# SharkPup-System.net
KiCad netlist of a schematic drawn in Altium Designer
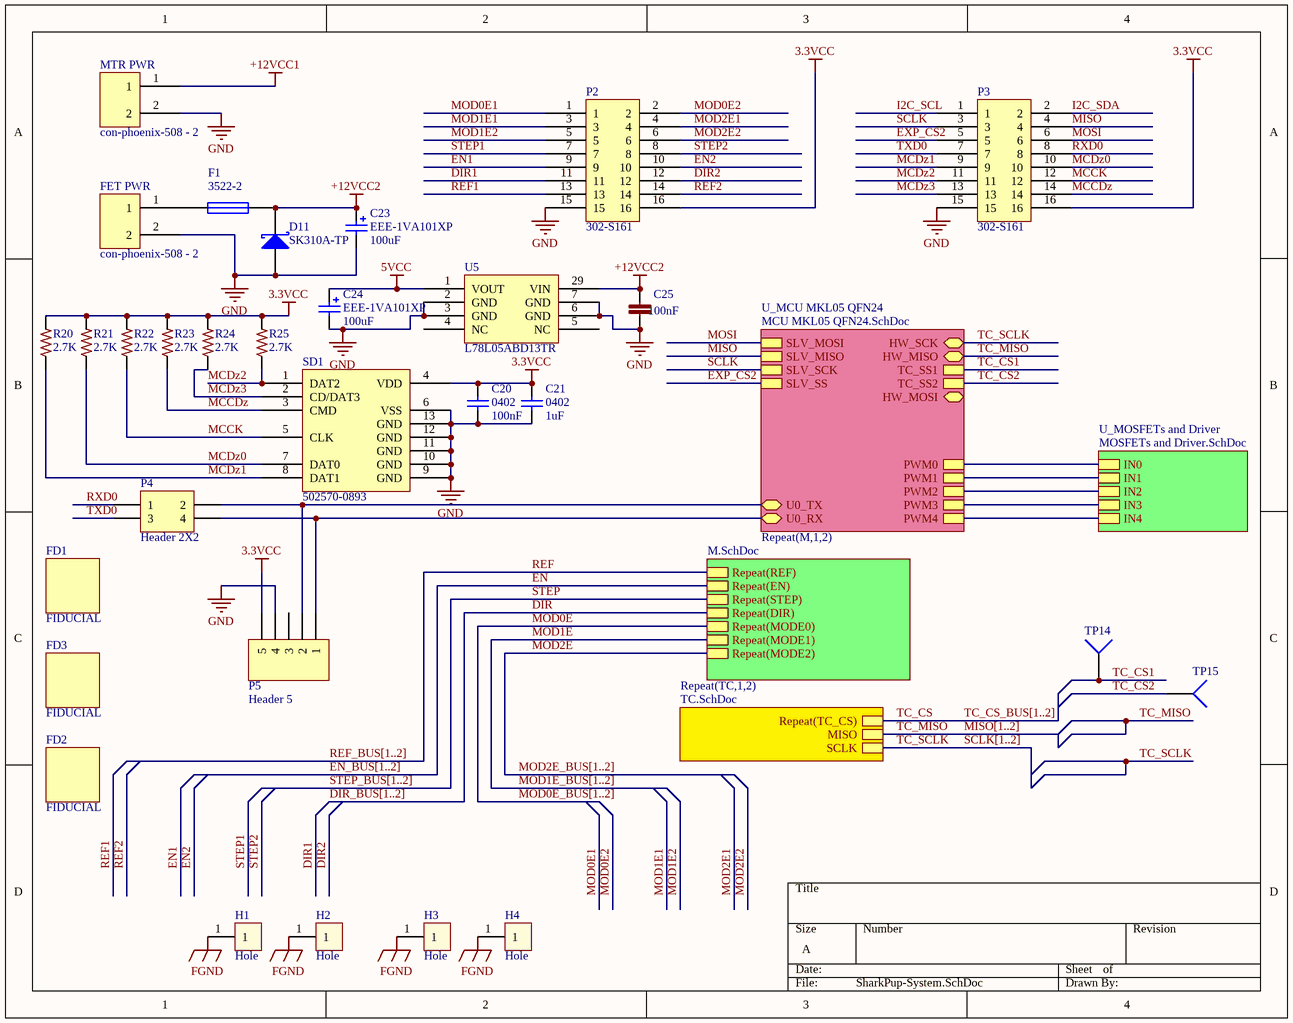
[diagram p0: SharkPup-System.SchDoc]

(export (version "E")
  (design (tool "Eeschema 10.0.6"))
  (components
    (comp (ref "C20")
      (value "100nF")
      (footprint "C0402")
      (description "CAP CER 0.1UF (100nF) 16V 10% X7R 0402")
      (fields
        (field (name "MFR PART #") "GRM155R71C104KA88D")
        (field (name "MFR") "Murata")
        (field (name "PACKAGEREFERENCE") "0402")
        (field (name "PUBLISHER") "Ultimachine")
      )
      (libsource (lib "Tigershark3D") (part "GRM155R71C104KA88D"))
    )
    (comp (ref "C21")
      (value "1uF")
      (footprint "C0402")
      (description "CAP CER 1UF 6.3V 10% X5R 0402")
      (fields
        (field (name "MFR PART #") "GRM155R60J105KE19D")
        (field (name "MFR") "Murata")
        (field (name "PACKAGEREFERENCE") "0402")
        (field (name "PUBLISHER") "Ultimachine")
      )
      (libsource (lib "Tigershark3D") (part "GRM155R60J105KE19D"))
    )
    (comp (ref "C23")
      (value "EEE-1VA101XP")
      (footprint "EEE-1VA101XP")
      (description "CAP ALUM 100UF 35V 20% SMD")
      (fields (field (name "DIGIKEY PART #") "PCE3951CT-ND") (field (name "ALTIUM_VALUE") "100uF"))
      (libsource (lib "Tigershark3D") (part "EEE-1VA101XP"))
    )
    (comp (ref "C24")
      (value "EEE-1VA101XP")
      (footprint "EEE-1VA101XP")
      (description "CAP ALUM 100UF 35V 20% SMD")
      (fields (field (name "DIGIKEY PART #") "PCE3951CT-ND") (field (name "ALTIUM_VALUE") "100uF"))
      (libsource (lib "Tigershark3D") (part "EEE-1VA101XP"))
    )
    (comp (ref "C25")
      (value "100nF")
      (footprint "C0603")
      (description "CAP CER 0603 100nF 50V 10% X7R")
      (fields
        (field (name "MANUFACTURERPARTNUMBER") "C0603C104K5RACTU")
        (field (name "PUBLISHER") "UltiMachine")
      )
      (libsource (lib "Tigershark3D") (part "C0603C104K5RACTU"))
    )
    (comp (ref "D11")
      (value "SK310A-TP")
      (footprint "SK310A-TP")
      (description "Schottky Diode")
      (fields (field (name "PUBLISHER") "Altium Limited"))
      (libsource (lib "Miscellaneous Devices") (part "D Schottky"))
    )
    (comp (ref "F1")
      (value "3522-2")
      (footprint "3522-2 - WAVE SOLDER")
      (description "Fuse")
      (fields (field (name "PUBLISHER") "Altium Limited"))
      (libsource (lib "Miscellaneous Devices") (part "Fuse 1"))
    )
    (comp (ref "FD1")
      (value "FIDUCIAL")
      (footprint "FIDUCIAL-1X2")
      (libsource (lib "ZMBo Schematic Library") (part "FIDUCIAL"))
    )
    (comp (ref "FD2")
      (value "FIDUCIAL")
      (footprint "FIDUCIAL-1X2")
      (libsource (lib "ZMBo Schematic Library") (part "FIDUCIAL"))
    )
    (comp (ref "FD3")
      (value "FIDUCIAL")
      (footprint "FIDUCIAL-1X2")
      (libsource (lib "ZMBo Schematic Library") (part "FIDUCIAL"))
    )
    (comp (ref "FET PWR")
      (value "con-phoenix-508 - 2")
      (footprint "MSTBV2 - duplicate")
      (libsource (lib "ZMBo Schematic Library") (part "con-phoenix-508_2"))
    )
    (comp (ref "H1")
      (value "Hole")
      (footprint "Wave_hole_3x7-singleSided")
      (libsource (lib "3Delight") (part "Hole"))
    )
    (comp (ref "H2")
      (value "Hole")
      (footprint "Wave_hole_3x7-singleSided")
      (libsource (lib "3Delight") (part "Hole"))
    )
    (comp (ref "H3")
      (value "Hole")
      (footprint "Wave_hole_3x7-singleSided")
      (libsource (lib "3Delight") (part "Hole"))
    )
    (comp (ref "H4")
      (value "Hole")
      (footprint "Wave_hole_3x7-singleSided")
      (libsource (lib "3Delight") (part "Hole"))
    )
    (comp (ref "MTR PWR")
      (value "con-phoenix-508 - 2")
      (footprint "MSTBV2 - duplicate")
      (libsource (lib "ZMBo Schematic Library") (part "con-phoenix-508_2"))
    )
    (comp (ref "P2")
      (value "302-S161")
      (footprint "302-S161")
      (description "16 Pos 2.54mm Pin Connector Shrouded")
      (fields (field (name "DIGIKEY PART #") "ED10522-ND"))
      (libsource (lib "Tigershark3D") (part "302-S161"))
    )
    (comp (ref "P3")
      (value "302-S161")
      (footprint "302-S161")
      (description "16 Pos 2.54mm Pin Connector Shrouded")
      (fields (field (name "DIGIKEY PART #") "ED10522-ND"))
      (libsource (lib "Tigershark3D") (part "302-S161"))
    )
    (comp (ref "P4")
      (value "Header 2X2")
      (footprint "HDR2X2")
      (description "Header, 2-Pin, Dual row")
      (fields (field (name "PUBLISHER") "Altium Limited"))
      (libsource (lib "Miscellaneous Connectors") (part "Header 2X2"))
    )
    (comp (ref "P5")
      (value "Header 5")
      (footprint "HDR1X5")
      (description "Header, 5-Pin")
      (fields (field (name "PUBLISHER") "Altium Limited"))
      (libsource (lib "Miscellaneous Connectors") (part "Header 5"))
    )
    (comp (ref "R20")
      (value "2.7K")
      (footprint "R0402")
      (description "RES SMD 2.7K OHM 1% 1/10W 0402")
      (fields
        (field (name "MANUFACTURER") "Panasonic")
        (field (name "MANUFACTURERPARTNUMBER") "ERJ2GEJ105X")
        (field (name "PUBLISHER") "Adam")
      )
      (libsource (lib "Tigershark3D") (part "ERJ-2RKF2701X"))
    )
    (comp (ref "R21")
      (value "2.7K")
      (footprint "R0402")
      (description "RES SMD 2.7K OHM 1% 1/10W 0402")
      (fields
        (field (name "MANUFACTURER") "Panasonic")
        (field (name "MANUFACTURERPARTNUMBER") "ERJ2GEJ105X")
        (field (name "PUBLISHER") "Adam")
      )
      (libsource (lib "Tigershark3D") (part "ERJ-2RKF2701X"))
    )
    (comp (ref "R22")
      (value "2.7K")
      (footprint "R0402")
      (description "RES SMD 2.7K OHM 1% 1/10W 0402")
      (fields
        (field (name "MANUFACTURER") "Panasonic")
        (field (name "MANUFACTURERPARTNUMBER") "ERJ2GEJ105X")
        (field (name "PUBLISHER") "Adam")
      )
      (libsource (lib "Tigershark3D") (part "ERJ-2RKF2701X"))
    )
    (comp (ref "R23")
      (value "2.7K")
      (footprint "R0402")
      (description "RES SMD 2.7K OHM 1% 1/10W 0402")
      (fields
        (field (name "MANUFACTURER") "Panasonic")
        (field (name "MANUFACTURERPARTNUMBER") "ERJ2GEJ105X")
        (field (name "PUBLISHER") "Adam")
      )
      (libsource (lib "Tigershark3D") (part "ERJ-2RKF2701X"))
    )
    (comp (ref "R24")
      (value "2.7K")
      (footprint "R0402")
      (description "RES SMD 2.7K OHM 1% 1/10W 0402")
      (fields
        (field (name "MANUFACTURER") "Panasonic")
        (field (name "MANUFACTURERPARTNUMBER") "ERJ2GEJ105X")
        (field (name "PUBLISHER") "Adam")
      )
      (libsource (lib "Tigershark3D") (part "ERJ-2RKF2701X"))
    )
    (comp (ref "R25")
      (value "2.7K")
      (footprint "R0402")
      (description "RES SMD 2.7K OHM 1% 1/10W 0402")
      (fields
        (field (name "MANUFACTURER") "Panasonic")
        (field (name "MANUFACTURERPARTNUMBER") "ERJ2GEJ105X")
        (field (name "PUBLISHER") "Adam")
      )
      (libsource (lib "Tigershark3D") (part "ERJ-2RKF2701X"))
    )
    (comp (ref "SD1")
      (value "502570-0893")
      (footprint "502570-0893 - Molex SD")
      (description "microSD 502570-0893 Molex Part")
      (libsource (lib "Tigershark3D") (part "502570-0893"))
    )
    (comp (ref "TP14")
      (value "TP4")
      (footprint "TP-2")
      (description "Socket")
      (fields (field (name "PUBLISHER") "Altium Limited"))
      (libsource (lib "ZMBo Schematic Library") (part "Socket"))
    )
    (comp (ref "TP15")
      (value "TP4")
      (footprint "TP-2")
      (description "Socket")
      (fields (field (name "PUBLISHER") "Altium Limited"))
      (libsource (lib "ZMBo Schematic Library") (part "Socket"))
    )
    (comp (ref "U5")
      (value "L78L05ABD13TR")
      (footprint "L78L05ABD13TR")
      (description "IC REG LDO 5V 0.1A 8SO")
      (fields (field (name "MANUFACTURER") "ST Microelectronics") (field (name "VOLTAGE") "30V"))
      (libsource (lib "SharkPup") (part "L78L05ABD13TR"))
    )
  )
  (nets
    (net (code "21") (name "+12VCC1") (class "Default")
      (node (ref "MTR PWR") (pin "1") (pinfunction "1_1") (pintype "passive"))
    )
    (net (code "22") (name "+12VCC2") (class "Default")
      (node (ref "C23") (pin "1") (pinfunction "1_1") (pintype "passive"))
      (node (ref "C25") (pin "1") (pinfunction "1_1") (pintype "passive"))
      (node (ref "D11") (pin "2") (pinfunction "K_2") (pintype "passive"))
      (node (ref "F1") (pin "2") (pinfunction "2_2") (pintype "passive"))
      (node (ref "U5") (pin "29") (pinfunction "VIN_29") (pintype "passive"))
    )
    (net (code "24") (name "/DIR1") (class "Default")
      (node (ref "P2") (pin "11") (pinfunction "11_11") (pintype "passive"))
    )
    (net (code "25") (name "/DIR2") (class "Default")
      (node (ref "P2") (pin "12") (pinfunction "12_12") (pintype "passive"))
    )
    (net (code "28") (name "/EN1") (class "Default")
      (node (ref "P2") (pin "9") (pinfunction "9_9") (pintype "passive"))
    )
    (net (code "29") (name "/EN2") (class "Default")
      (node (ref "P2") (pin "10") (pinfunction "10_10") (pintype "passive"))
    )
    (net (code "31") (name "/EXP_CS2") (class "Default")
      (node (ref "P3") (pin "5") (pinfunction "5_5") (pintype "passive"))
    )
    (net (code "33") (name "/I2C_SCL") (class "Default")
      (node (ref "P3") (pin "1") (pinfunction "1_1") (pintype "passive"))
    )
    (net (code "34") (name "/I2C_SDA") (class "Default")
      (node (ref "P3") (pin "2") (pinfunction "2_2") (pintype "passive"))
    )
    (net (code "40") (name "/MCCDz") (class "Default")
      (node (ref "P3") (pin "14") (pinfunction "14_14") (pintype "passive"))
      (node (ref "R23") (pin "1") (pinfunction "1_1") (pintype "passive"))
      (node (ref "SD1") (pin "3") (pinfunction "CMD_3") (pintype "passive"))
    )
    (net (code "41") (name "/MCCK") (class "Default")
      (node (ref "P3") (pin "12") (pinfunction "12_12") (pintype "passive"))
      (node (ref "R22") (pin "1") (pinfunction "1_1") (pintype "passive"))
      (node (ref "SD1") (pin "5") (pinfunction "CLK_5") (pintype "passive"))
    )
    (net (code "42") (name "/MCDz0") (class "Default")
      (node (ref "P3") (pin "10") (pinfunction "10_10") (pintype "passive"))
      (node (ref "R21") (pin "1") (pinfunction "1_1") (pintype "passive"))
      (node (ref "SD1") (pin "7") (pinfunction "DAT0_7") (pintype "passive"))
    )
    (net (code "43") (name "/MCDz1") (class "Default")
      (node (ref "P3") (pin "9") (pinfunction "9_9") (pintype "passive"))
      (node (ref "R20") (pin "1") (pinfunction "1_1") (pintype "passive"))
      (node (ref "SD1") (pin "8") (pinfunction "DAT1_8") (pintype "passive"))
    )
    (net (code "44") (name "/MCDz2") (class "Default")
      (node (ref "P3") (pin "11") (pinfunction "11_11") (pintype "passive"))
      (node (ref "R25") (pin "1") (pinfunction "1_1") (pintype "passive"))
      (node (ref "SD1") (pin "1") (pinfunction "DAT2_1") (pintype "passive"))
    )
    (net (code "45") (name "/MCDz3") (class "Default")
      (node (ref "P3") (pin "13") (pinfunction "13_13") (pintype "passive"))
      (node (ref "R24") (pin "1") (pinfunction "1_1") (pintype "passive"))
      (node (ref "SD1") (pin "2") (pinfunction "CD/DAT3_2") (pintype "passive"))
    )
    (net (code "46") (name "/MISO") (class "Default")
      (node (ref "P3") (pin "4") (pinfunction "4_4") (pintype "passive"))
    )
    (net (code "49") (name "/MOD0E1") (class "Default")
      (node (ref "P2") (pin "1") (pinfunction "1_1") (pintype "passive"))
    )
    (net (code "50") (name "/MOD0E2") (class "Default")
      (node (ref "P2") (pin "2") (pinfunction "2_2") (pintype "passive"))
    )
    (net (code "53") (name "/MOD1E1") (class "Default")
      (node (ref "P2") (pin "3") (pinfunction "3_3") (pintype "passive"))
    )
    (net (code "54") (name "/MOD1E2") (class "Default")
      (node (ref "P2") (pin "5") (pinfunction "5_5") (pintype "passive"))
    )
    (net (code "57") (name "/MOD2E1") (class "Default")
      (node (ref "P2") (pin "4") (pinfunction "4_4") (pintype "passive"))
    )
    (net (code "58") (name "/MOD2E2") (class "Default")
      (node (ref "P2") (pin "6") (pinfunction "6_6") (pintype "passive"))
    )
    (net (code "60") (name "/MOSI") (class "Default")
      (node (ref "P3") (pin "6") (pinfunction "6_6") (pintype "passive"))
    )
    (net (code "62") (name "/REF1") (class "Default")
      (node (ref "P2") (pin "13") (pinfunction "13_13") (pintype "passive"))
    )
    (net (code "63") (name "/REF2") (class "Default")
      (node (ref "P2") (pin "14") (pinfunction "14_14") (pintype "passive"))
    )
    (net (code "65") (name "/RXD0") (class "Default")
      (node (ref "P3") (pin "8") (pinfunction "8_8") (pintype "passive"))
      (node (ref "P4") (pin "1") (pinfunction "1_1") (pintype "passive"))
    )
    (net (code "66") (name "/SCLK") (class "Default")
      (node (ref "P3") (pin "3") (pinfunction "3_3") (pintype "passive"))
    )
    (net (code "69") (name "/STEP1") (class "Default")
      (node (ref "P2") (pin "7") (pinfunction "7_7") (pintype "passive"))
    )
    (net (code "70") (name "/STEP2") (class "Default")
      (node (ref "P2") (pin "8") (pinfunction "8_8") (pintype "passive"))
    )
    (net (code "73") (name "/TC_CS1") (class "Default")
      (node (ref "TP14") (pin "1") (pinfunction "1_1") (pintype "passive"))
    )
    (net (code "74") (name "/TC_CS2") (class "Default")
      (node (ref "TP15") (pin "1") (pinfunction "1_1") (pintype "passive"))
    )
    (net (code "78") (name "/TXD0") (class "Default")
      (node (ref "P3") (pin "7") (pinfunction "7_7") (pintype "passive"))
      (node (ref "P4") (pin "3") (pinfunction "3_3") (pintype "passive"))
    )
    (net (code "79") (name "/U0_RX") (class "Default")
      (node (ref "P4") (pin "4") (pinfunction "4_4") (pintype "passive"))
      (node (ref "P5") (pin "1") (pinfunction "1_1") (pintype "passive"))
    )
    (net (code "80") (name "/U0_TX") (class "Default")
      (node (ref "P4") (pin "2") (pinfunction "2_2") (pintype "passive"))
      (node (ref "P5") (pin "2") (pinfunction "2_2") (pintype "passive"))
    )
    (net (code "81") (name "3.3VCC") (class "Default")
      (node (ref "C20") (pin "2") (pinfunction "2_2") (pintype "passive"))
      (node (ref "C21") (pin "2") (pinfunction "2_2") (pintype "passive"))
      (node (ref "P2") (pin "16") (pinfunction "16_16") (pintype "passive"))
      (node (ref "P3") (pin "16") (pinfunction "16_16") (pintype "passive"))
      (node (ref "P5") (pin "5") (pinfunction "5_5") (pintype "passive"))
      (node (ref "R20") (pin "2") (pinfunction "2_2") (pintype "passive"))
      (node (ref "R21") (pin "2") (pinfunction "2_2") (pintype "passive"))
      (node (ref "R22") (pin "2") (pinfunction "2_2") (pintype "passive"))
      (node (ref "R23") (pin "2") (pinfunction "2_2") (pintype "passive"))
      (node (ref "R24") (pin "2") (pinfunction "2_2") (pintype "passive"))
      (node (ref "R25") (pin "2") (pinfunction "2_2") (pintype "passive"))
      (node (ref "SD1") (pin "4") (pinfunction "VDD_4") (pintype "passive"))
    )
    (net (code "82") (name "5VCC") (class "Default")
      (node (ref "C24") (pin "1") (pinfunction "1_1") (pintype "passive"))
      (node (ref "U5") (pin "1") (pinfunction "VOUT_1") (pintype "passive"))
    )
    (net (code "83") (name "FGND") (class "Default")
      (node (ref "H1") (pin "1") (pinfunction "1_1") (pintype "power_in"))
      (node (ref "H2") (pin "1") (pinfunction "1_1") (pintype "power_in"))
      (node (ref "H3") (pin "1") (pinfunction "1_1") (pintype "power_in"))
      (node (ref "H4") (pin "1") (pinfunction "1_1") (pintype "power_in"))
    )
    (net (code "84") (name "GND") (class "Default")
      (node (ref "C20") (pin "1") (pinfunction "1_1") (pintype "passive"))
      (node (ref "C21") (pin "1") (pinfunction "1_1") (pintype "passive"))
      (node (ref "C23") (pin "2") (pinfunction "2_2") (pintype "passive"))
      (node (ref "C24") (pin "2") (pinfunction "2_2") (pintype "passive"))
      (node (ref "C25") (pin "2") (pinfunction "2_2") (pintype "passive"))
      (node (ref "D11") (pin "1") (pinfunction "A_1") (pintype "passive"))
      (node (ref "FET PWR") (pin "2") (pinfunction "2_2") (pintype "passive"))
      (node (ref "MTR PWR") (pin "2") (pinfunction "2_2") (pintype "passive"))
      (node (ref "P2") (pin "15") (pinfunction "15_15") (pintype "passive"))
      (node (ref "P3") (pin "15") (pinfunction "15_15") (pintype "passive"))
      (node (ref "P5") (pin "4") (pinfunction "4_4") (pintype "passive"))
      (node (ref "SD1") (pin "10") (pinfunction "GND_10") (pintype "passive"))
      (node (ref "SD1") (pin "11") (pinfunction "GND_11") (pintype "passive"))
      (node (ref "SD1") (pin "12") (pinfunction "GND_12") (pintype "passive"))
      (node (ref "SD1") (pin "13") (pinfunction "GND_13") (pintype "passive"))
      (node (ref "SD1") (pin "6") (pinfunction "VSS_6") (pintype "passive"))
      (node (ref "SD1") (pin "9") (pinfunction "GND_9") (pintype "passive"))
      (node (ref "U5") (pin "2") (pinfunction "GND_2") (pintype "passive"))
      (node (ref "U5") (pin "3") (pinfunction "GND_3") (pintype "passive"))
      (node (ref "U5") (pin "6") (pinfunction "GND_6") (pintype "passive"))
      (node (ref "U5") (pin "7") (pinfunction "GND_7") (pintype "passive"))
    )
    (net (code "85") (name "Net-(F1-Pad1)") (class "Default")
      (node (ref "F1") (pin "1") (pinfunction "1_1") (pintype "passive"))
      (node (ref "FET PWR") (pin "1") (pinfunction "1_1") (pintype "passive"))
    )
    (net (code "86") (name "unconnected-(P5-Pad3)") (class "Default")
      (node (ref "P5") (pin "3") (pinfunction "3_3") (pintype "passive"))
    )
    (net (code "87") (name "unconnected-(U5-NC-Pad4)") (class "Default")
      (node (ref "U5") (pin "4") (pinfunction "NC_4") (pintype "passive"))
    )
    (net (code "88") (name "unconnected-(U5-NC-Pad5)") (class "Default")
      (node (ref "U5") (pin "5") (pinfunction "NC_5") (pintype "passive"))
    )
    (net (code "89") (name "unconnected-(U5-NC-Pad23)") (class "Default")
      (node (ref "U5") (pin "23") (pinfunction "NC_23") (pintype "passive"))
    )
  )
)
